# LEDRing.net
KiCad netlist of a schematic drawn in EAGLE
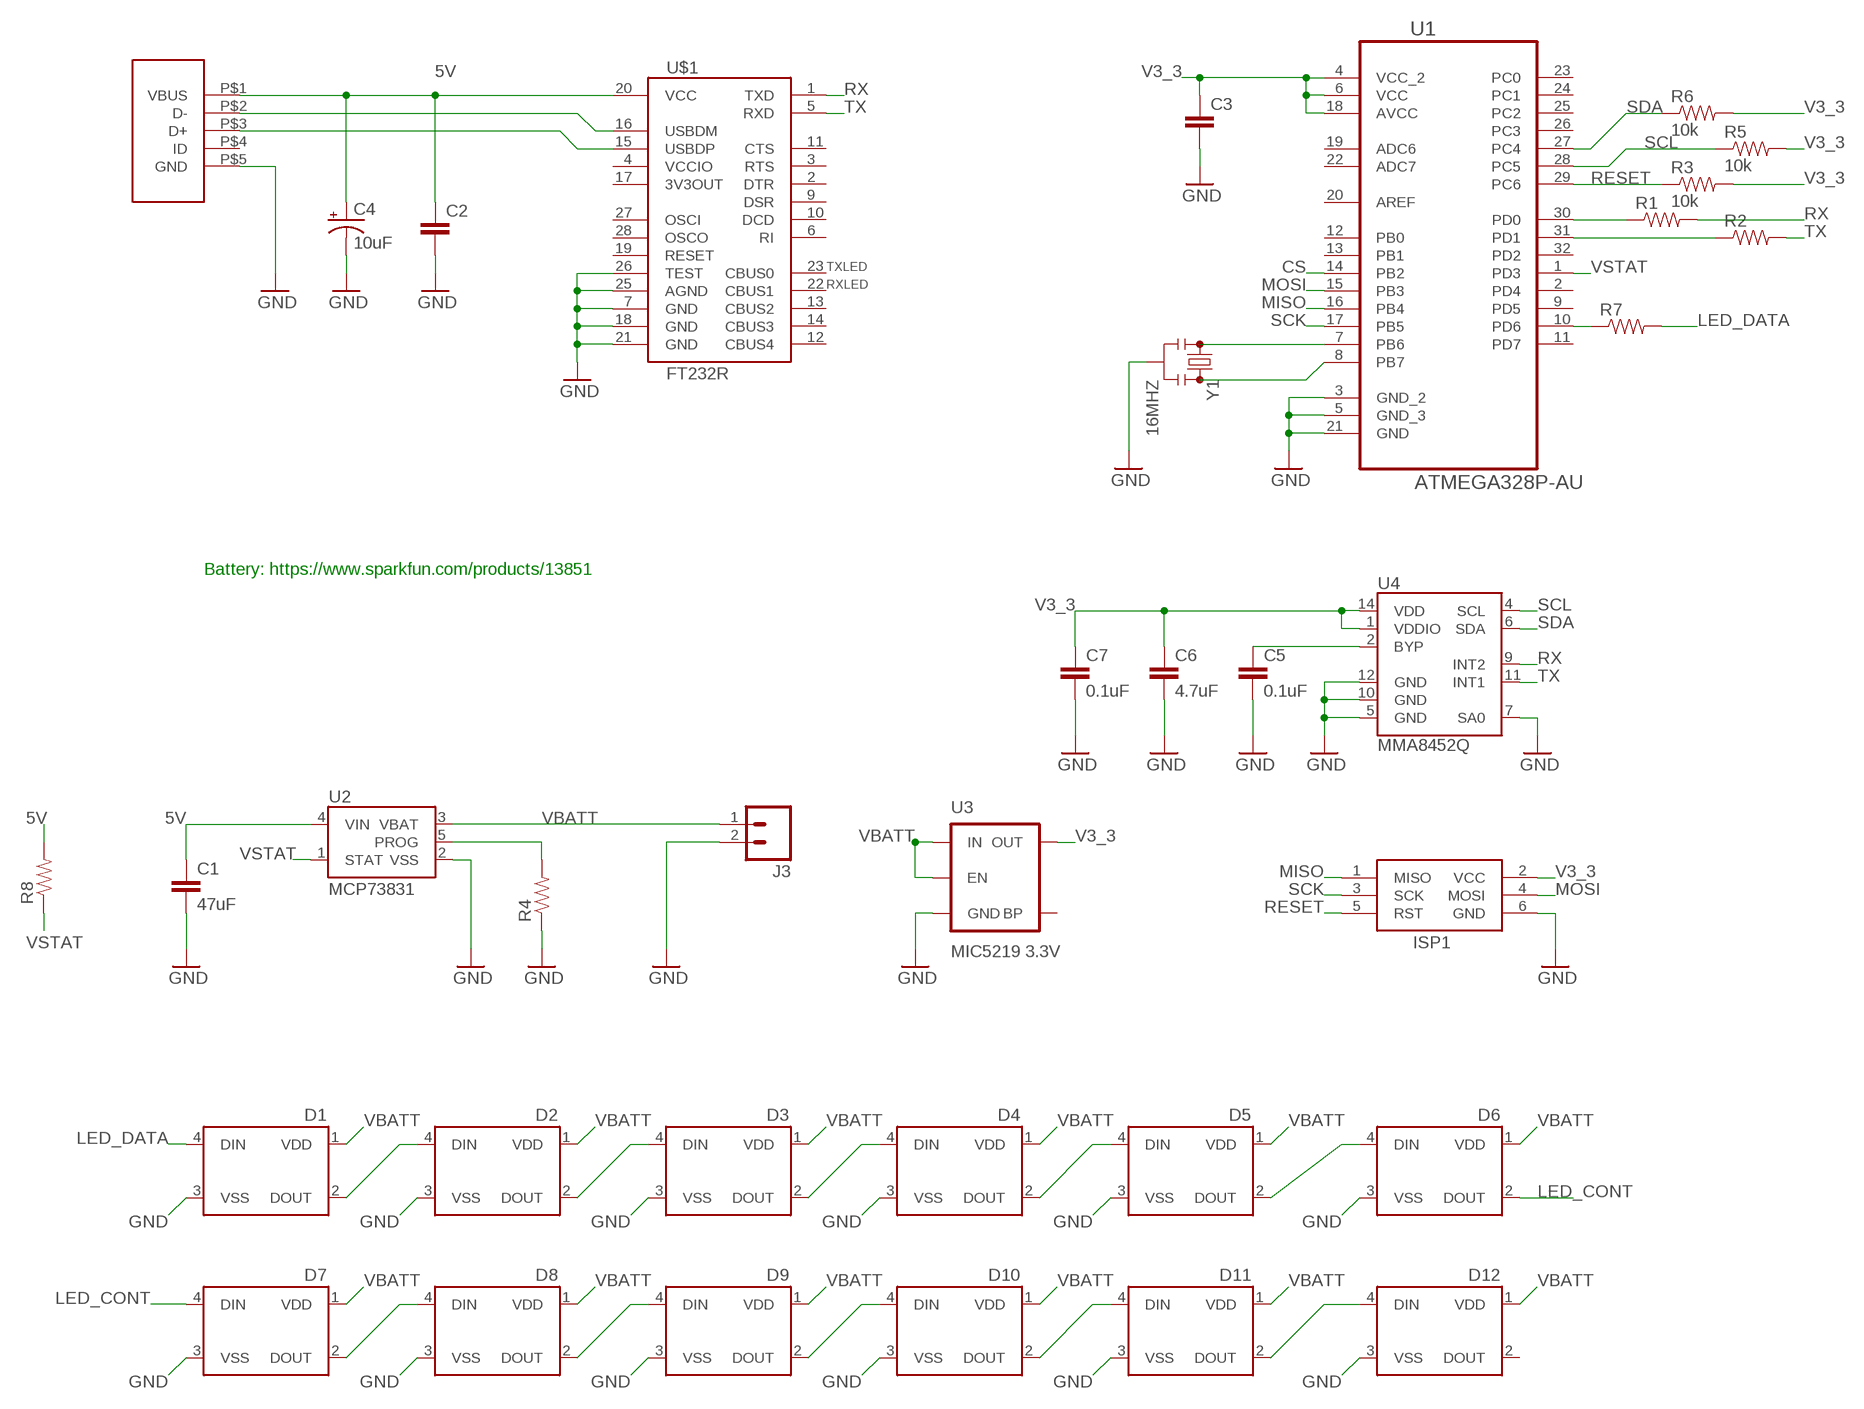
[diagram p0: schematic, sheet 1]

(export (version "E")
  (design (tool "Eeschema 10.0.6"))
  (components
    (comp (ref "C1")
      (value "47uF")
      (footprint "eagle-import:0603-CAP")
      (libsource (lib "eagle-import") (part "CAP0603-CAP"))
    )
    (comp (ref "C2")
      (value "CAP0603-CAP")
      (footprint "eagle-import:0603-CAP")
      (libsource (lib "eagle-import") (part "CAP0603-CAP"))
    )
    (comp (ref "C3")
      (value "CAP0603-CAP")
      (footprint "eagle-import:0603-CAP")
      (libsource (lib "eagle-import") (part "CAP0603-CAP"))
    )
    (comp (ref "C4")
      (value "10uF")
      (footprint "eagle-import:0603-POL")
      (libsource (lib "eagle-import") (part "10UF-6.3V-20%(0603)(TANT){dblquote}"))
    )
    (comp (ref "C5")
      (value "0.1uF")
      (footprint "eagle-import:0603-CAP")
      (libsource (lib "eagle-import") (part "CAP0603-CAP"))
    )
    (comp (ref "C6")
      (value "4.7uF")
      (footprint "eagle-import:0603-CAP")
      (libsource (lib "eagle-import") (part "CAP0603-CAP"))
    )
    (comp (ref "C7")
      (value "0.1uF")
      (footprint "eagle-import:0603-CAP")
      (libsource (lib "eagle-import") (part "CAP0603-CAP"))
    )
    (comp (ref "D1")
      (value "WS2812B")
      (footprint "eagle-import:WS2812B")
      (libsource (lib "eagle-import") (part "WS2812B"))
    )
    (comp (ref "D2")
      (value "WS2812B")
      (footprint "eagle-import:WS2812B")
      (libsource (lib "eagle-import") (part "WS2812B"))
    )
    (comp (ref "D3")
      (value "WS2812B")
      (footprint "eagle-import:WS2812B")
      (libsource (lib "eagle-import") (part "WS2812B"))
    )
    (comp (ref "D4")
      (value "WS2812B")
      (footprint "eagle-import:WS2812B")
      (libsource (lib "eagle-import") (part "WS2812B"))
    )
    (comp (ref "D5")
      (value "WS2812B")
      (footprint "eagle-import:WS2812B")
      (libsource (lib "eagle-import") (part "WS2812B"))
    )
    (comp (ref "D6")
      (value "WS2812B")
      (footprint "eagle-import:WS2812B")
      (libsource (lib "eagle-import") (part "WS2812B"))
    )
    (comp (ref "D7")
      (value "WS2812B")
      (footprint "eagle-import:WS2812B")
      (libsource (lib "eagle-import") (part "WS2812B"))
    )
    (comp (ref "D8")
      (value "WS2812B")
      (footprint "eagle-import:WS2812B")
      (libsource (lib "eagle-import") (part "WS2812B"))
    )
    (comp (ref "D9")
      (value "WS2812B")
      (footprint "eagle-import:WS2812B")
      (libsource (lib "eagle-import") (part "WS2812B"))
    )
    (comp (ref "D10")
      (value "WS2812B")
      (footprint "eagle-import:WS2812B")
      (libsource (lib "eagle-import") (part "WS2812B"))
    )
    (comp (ref "D11")
      (value "WS2812B")
      (footprint "eagle-import:WS2812B")
      (libsource (lib "eagle-import") (part "WS2812B"))
    )
    (comp (ref "D12")
      (value "WS2812B")
      (footprint "eagle-import:WS2812B")
      (libsource (lib "eagle-import") (part "WS2812B"))
    )
    (comp (ref "ISP1")
      (value "AVRISP-BOX")
      (footprint "eagle-import:AVRISP-BOX")
      (libsource (lib "eagle-import") (part "AVRISP-BOX"))
    )
    (comp (ref "J3")
      (value "M02PTH")
      (footprint "eagle-import:1X02")
      (libsource (lib "eagle-import") (part "M02PTH"))
    )
    (comp (ref "R1")
      (value "RESISTOR0603-RES")
      (footprint "eagle-import:0603-RES")
      (libsource (lib "eagle-import") (part "RESISTOR0603-RES"))
    )
    (comp (ref "R2")
      (value "RESISTOR0603-RES")
      (footprint "eagle-import:0603-RES")
      (libsource (lib "eagle-import") (part "RESISTOR0603-RES"))
    )
    (comp (ref "R3")
      (value "10k")
      (footprint "eagle-import:0603-RES")
      (libsource (lib "eagle-import") (part "RESISTOR0603-RES"))
    )
    (comp (ref "R4")
      (value "RESISTOR0603-RES")
      (footprint "eagle-import:0603-RES")
      (libsource (lib "eagle-import") (part "RESISTOR0603-RES"))
    )
    (comp (ref "R5")
      (value "10k")
      (footprint "eagle-import:0603-RES")
      (libsource (lib "eagle-import") (part "RESISTOR0603-RES"))
    )
    (comp (ref "R6")
      (value "10k")
      (footprint "eagle-import:0603-RES")
      (libsource (lib "eagle-import") (part "RESISTOR0603-RES"))
    )
    (comp (ref "R7")
      (value "RESISTOR0603-RES")
      (footprint "eagle-import:0603-RES")
      (libsource (lib "eagle-import") (part "RESISTOR0603-RES"))
    )
    (comp (ref "R8")
      (value "RESISTOR0603-RES")
      (footprint "eagle-import:0603-RES")
      (libsource (lib "eagle-import") (part "RESISTOR0603-RES"))
    )
    (comp (ref "U$1")
      (value "FT232R")
      (footprint "eagle-import:SSOP-28")
      (libsource (lib "eagle-import") (part "FT232R"))
    )
    (comp (ref "U$2")
      (value "TE_USB_A121025CT")
      (footprint "eagle-import:TE_USB_A121025CT")
      (libsource (lib "eagle-import") (part "TE_USB_A121025CT"))
    )
    (comp (ref "U1")
      (value "ATMEGA328P-AU")
      (footprint "eagle-import:QFP80P900X900X120-32N")
      (libsource (lib "eagle-import") (part "ATMEGA328P-AU"))
    )
    (comp (ref "U2")
      (value "MCP73831")
      (footprint "eagle-import:SOT23-5")
      (libsource (lib "eagle-import") (part "MCP73831"))
    )
    (comp (ref "U3")
      (value "MIC5219 3.3V")
      (footprint "eagle-import:SOT23-5")
      (libsource (lib "eagle-import") (part "V_REG_MIC52193.3V"))
    )
    (comp (ref "U4")
      (value "MMA8452Q")
      (footprint "eagle-import:QFN-16_0.5MM")
      (libsource (lib "eagle-import") (part "MMA8452Q"))
    )
    (comp (ref "Y1")
      (value "16MHZ")
      (footprint "eagle-import:RESONATOR-SMD")
      (libsource (lib "eagle-import") (part "RESONATOR16MHZ"))
    )
  )
  (nets
    (net (code "1") (name "/5V") (class "Default")
      (node (ref "C1") (pin "1") (pinfunction "1_1") (pintype "passive"))
      (node (ref "C2") (pin "1") (pinfunction "1_1") (pintype "passive"))
      (node (ref "C4") (pin "A") (pinfunction "+_A") (pintype "passive"))
      (node (ref "R8") (pin "2") (pinfunction "2_2") (pintype "passive"))
      (node (ref "U$1") (pin "20") (pinfunction "VCC_20") (pintype "power_in"))
      (node (ref "U$2") (pin "P$1") (pinfunction "VBUS_P$1") (pintype "bidirectional"))
      (node (ref "U2") (pin "4") (pinfunction "VIN_4") (pintype "power_in"))
    )
    (net (code "2") (name "/CS") (class "Default")
      (node (ref "U1") (pin "14") (pinfunction "PB2_14") (pintype "bidirectional"))
    )
    (net (code "3") (name "/LED_CONT") (class "Default")
      (node (ref "D6") (pin "2") (pinfunction "DOUT_2") (pintype "output"))
      (node (ref "D7") (pin "4") (pinfunction "DIN_4") (pintype "input"))
    )
    (net (code "4") (name "/LED_DATA") (class "Default")
      (node (ref "D1") (pin "4") (pinfunction "DIN_4") (pintype "input"))
      (node (ref "R7") (pin "2") (pinfunction "2_2") (pintype "passive"))
    )
    (net (code "5") (name "/MISO") (class "Default")
      (node (ref "ISP1") (pin "1") (pinfunction "MISO_1") (pintype "input"))
      (node (ref "U1") (pin "16") (pinfunction "PB4_16") (pintype "bidirectional"))
    )
    (net (code "6") (name "/MOSI") (class "Default")
      (node (ref "ISP1") (pin "4") (pinfunction "MOSI_4") (pintype "output"))
      (node (ref "U1") (pin "15") (pinfunction "PB3_15") (pintype "bidirectional"))
    )
    (net (code "7") (name "/RESET") (class "Default")
      (node (ref "ISP1") (pin "5") (pinfunction "RST_5") (pintype "output"))
      (node (ref "R3") (pin "1") (pinfunction "1_1") (pintype "passive"))
      (node (ref "U1") (pin "29") (pinfunction "PC6_29") (pintype "bidirectional"))
    )
    (net (code "8") (name "/RX") (class "Default")
      (node (ref "R1") (pin "2") (pinfunction "2_2") (pintype "passive"))
      (node (ref "U$1") (pin "1") (pinfunction "TXD_1") (pintype "output"))
      (node (ref "U4") (pin "9") (pinfunction "INT2_9") (pintype "bidirectional"))
    )
    (net (code "9") (name "/SCK") (class "Default")
      (node (ref "ISP1") (pin "3") (pinfunction "SCK_3") (pintype "output"))
      (node (ref "U1") (pin "17") (pinfunction "PB5_17") (pintype "bidirectional"))
    )
    (net (code "10") (name "/SCL") (class "Default")
      (node (ref "R5") (pin "1") (pinfunction "1_1") (pintype "passive"))
      (node (ref "U1") (pin "28") (pinfunction "PC5_28") (pintype "bidirectional"))
      (node (ref "U4") (pin "4") (pinfunction "SCL_4") (pintype "bidirectional"))
    )
    (net (code "11") (name "/SDA") (class "Default")
      (node (ref "R6") (pin "1") (pinfunction "1_1") (pintype "passive"))
      (node (ref "U1") (pin "27") (pinfunction "PC4_27") (pintype "bidirectional"))
      (node (ref "U4") (pin "6") (pinfunction "SDA_6") (pintype "bidirectional"))
    )
    (net (code "12") (name "/TX") (class "Default")
      (node (ref "R2") (pin "2") (pinfunction "2_2") (pintype "passive"))
      (node (ref "U$1") (pin "5") (pinfunction "RXD_5") (pintype "input"))
      (node (ref "U4") (pin "11") (pinfunction "INT1_11") (pintype "bidirectional"))
    )
    (net (code "13") (name "/V3_3") (class "Default")
      (node (ref "C3") (pin "1") (pinfunction "1_1") (pintype "passive"))
      (node (ref "C6") (pin "1") (pinfunction "1_1") (pintype "passive"))
      (node (ref "C7") (pin "1") (pinfunction "1_1") (pintype "passive"))
      (node (ref "ISP1") (pin "2") (pinfunction "VCC_2") (pintype "power_in"))
      (node (ref "R3") (pin "2") (pinfunction "2_2") (pintype "passive"))
      (node (ref "R5") (pin "2") (pinfunction "2_2") (pintype "passive"))
      (node (ref "R6") (pin "2") (pinfunction "2_2") (pintype "passive"))
      (node (ref "U1") (pin "18") (pinfunction "AVCC_18") (pintype "power_in"))
      (node (ref "U1") (pin "4") (pinfunction "VCC_2_4") (pintype "power_in"))
      (node (ref "U1") (pin "6") (pinfunction "VCC_6") (pintype "power_in"))
      (node (ref "U3") (pin "5") (pinfunction "OUT_5") (pintype "passive"))
      (node (ref "U4") (pin "1") (pinfunction "VDDIO_1") (pintype "bidirectional"))
      (node (ref "U4") (pin "14") (pinfunction "VDD_14") (pintype "bidirectional"))
    )
    (net (code "14") (name "/VBATT") (class "Default")
      (node (ref "D1") (pin "1") (pinfunction "VDD_1") (pintype "power_in"))
      (node (ref "D10") (pin "1") (pinfunction "VDD_1") (pintype "power_in"))
      (node (ref "D11") (pin "1") (pinfunction "VDD_1") (pintype "power_in"))
      (node (ref "D12") (pin "1") (pinfunction "VDD_1") (pintype "power_in"))
      (node (ref "D2") (pin "1") (pinfunction "VDD_1") (pintype "power_in"))
      (node (ref "D3") (pin "1") (pinfunction "VDD_1") (pintype "power_in"))
      (node (ref "D4") (pin "1") (pinfunction "VDD_1") (pintype "power_in"))
      (node (ref "D5") (pin "1") (pinfunction "VDD_1") (pintype "power_in"))
      (node (ref "D6") (pin "1") (pinfunction "VDD_1") (pintype "power_in"))
      (node (ref "D7") (pin "1") (pinfunction "VDD_1") (pintype "power_in"))
      (node (ref "D8") (pin "1") (pinfunction "VDD_1") (pintype "power_in"))
      (node (ref "D9") (pin "1") (pinfunction "VDD_1") (pintype "power_in"))
      (node (ref "J3") (pin "1") (pinfunction "1_1") (pintype "passive"))
      (node (ref "U2") (pin "3") (pinfunction "VBAT_3") (pintype "power_in"))
      (node (ref "U3") (pin "1") (pinfunction "IN_1") (pintype "input"))
      (node (ref "U3") (pin "3") (pinfunction "EN_3") (pintype "input"))
    )
    (net (code "15") (name "/VCCIO") (class "Default")
      (node (ref "U$1") (pin "4") (pinfunction "VCCIO_4") (pintype "power_in"))
    )
    (net (code "16") (name "/VSTAT") (class "Default")
      (node (ref "R8") (pin "1") (pinfunction "1_1") (pintype "passive"))
      (node (ref "U1") (pin "1") (pinfunction "PD3_1") (pintype "bidirectional"))
      (node (ref "U2") (pin "1") (pinfunction "STAT_1") (pintype "output"))
    )
    (net (code "17") (name "GND") (class "Default")
      (node (ref "C1") (pin "2") (pinfunction "2_2") (pintype "passive"))
      (node (ref "C2") (pin "2") (pinfunction "2_2") (pintype "passive"))
      (node (ref "C3") (pin "2") (pinfunction "2_2") (pintype "passive"))
      (node (ref "C4") (pin "K") (pinfunction "-_K") (pintype "passive"))
      (node (ref "C5") (pin "2") (pinfunction "2_2") (pintype "passive"))
      (node (ref "C6") (pin "2") (pinfunction "2_2") (pintype "passive"))
      (node (ref "C7") (pin "2") (pinfunction "2_2") (pintype "passive"))
      (node (ref "D1") (pin "3") (pinfunction "VSS_3") (pintype "power_in"))
      (node (ref "D10") (pin "3") (pinfunction "VSS_3") (pintype "power_in"))
      (node (ref "D11") (pin "3") (pinfunction "VSS_3") (pintype "power_in"))
      (node (ref "D12") (pin "3") (pinfunction "VSS_3") (pintype "power_in"))
      (node (ref "D2") (pin "3") (pinfunction "VSS_3") (pintype "power_in"))
      (node (ref "D3") (pin "3") (pinfunction "VSS_3") (pintype "power_in"))
      (node (ref "D4") (pin "3") (pinfunction "VSS_3") (pintype "power_in"))
      (node (ref "D5") (pin "3") (pinfunction "VSS_3") (pintype "power_in"))
      (node (ref "D6") (pin "3") (pinfunction "VSS_3") (pintype "power_in"))
      (node (ref "D7") (pin "3") (pinfunction "VSS_3") (pintype "power_in"))
      (node (ref "D8") (pin "3") (pinfunction "VSS_3") (pintype "power_in"))
      (node (ref "D9") (pin "3") (pinfunction "VSS_3") (pintype "power_in"))
      (node (ref "ISP1") (pin "6") (pinfunction "GND_6") (pintype "power_in"))
      (node (ref "J3") (pin "2") (pinfunction "2_2") (pintype "passive"))
      (node (ref "R4") (pin "1") (pinfunction "1_1") (pintype "passive"))
      (node (ref "U$1") (pin "18") (pinfunction "GND_18") (pintype "power_in"))
      (node (ref "U$1") (pin "21") (pinfunction "GND_21") (pintype "power_in"))
      (node (ref "U$1") (pin "25") (pinfunction "AGND_25") (pintype "power_in"))
      (node (ref "U$1") (pin "26") (pinfunction "TEST_26") (pintype "input"))
      (node (ref "U$1") (pin "7") (pinfunction "GND_7") (pintype "power_in"))
      (node (ref "U$2") (pin "P$5") (pinfunction "GND_P$5") (pintype "bidirectional"))
      (node (ref "U1") (pin "21") (pinfunction "GND_21") (pintype "passive"))
      (node (ref "U1") (pin "3") (pinfunction "GND_2_3") (pintype "passive"))
      (node (ref "U1") (pin "5") (pinfunction "GND_3_5") (pintype "passive"))
      (node (ref "U2") (pin "2") (pinfunction "VSS_2") (pintype "power_in"))
      (node (ref "U3") (pin "2") (pinfunction "GND_2") (pintype "input"))
      (node (ref "U4") (pin "10") (pinfunction "GND_10") (pintype "bidirectional"))
      (node (ref "U4") (pin "12") (pinfunction "GND_12") (pintype "bidirectional"))
      (node (ref "U4") (pin "5") (pinfunction "GND_5") (pintype "bidirectional"))
      (node (ref "U4") (pin "7") (pinfunction "SA0_7") (pintype "bidirectional"))
      (node (ref "Y1") (pin "2") (pinfunction "2_2") (pintype "passive"))
    )
    (net (code "18") (name "Net-(D1-DOUT)") (class "Default")
      (node (ref "D1") (pin "2") (pinfunction "DOUT_2") (pintype "output"))
      (node (ref "D2") (pin "4") (pinfunction "DIN_4") (pintype "input"))
    )
    (net (code "19") (name "Net-(D2-DOUT)") (class "Default")
      (node (ref "D2") (pin "2") (pinfunction "DOUT_2") (pintype "output"))
      (node (ref "D3") (pin "4") (pinfunction "DIN_4") (pintype "input"))
    )
    (net (code "20") (name "Net-(D3-DOUT)") (class "Default")
      (node (ref "D3") (pin "2") (pinfunction "DOUT_2") (pintype "output"))
      (node (ref "D4") (pin "4") (pinfunction "DIN_4") (pintype "input"))
    )
    (net (code "21") (name "Net-(D4-DOUT)") (class "Default")
      (node (ref "D4") (pin "2") (pinfunction "DOUT_2") (pintype "output"))
      (node (ref "D5") (pin "4") (pinfunction "DIN_4") (pintype "input"))
    )
    (net (code "22") (name "Net-(D5-DOUT)") (class "Default")
      (node (ref "D5") (pin "2") (pinfunction "DOUT_2") (pintype "output"))
      (node (ref "D6") (pin "4") (pinfunction "DIN_4") (pintype "input"))
    )
    (net (code "23") (name "Net-(D7-DOUT)") (class "Default")
      (node (ref "D7") (pin "2") (pinfunction "DOUT_2") (pintype "output"))
      (node (ref "D8") (pin "4") (pinfunction "DIN_4") (pintype "input"))
    )
    (net (code "24") (name "Net-(D8-DOUT)") (class "Default")
      (node (ref "D8") (pin "2") (pinfunction "DOUT_2") (pintype "output"))
      (node (ref "D9") (pin "4") (pinfunction "DIN_4") (pintype "input"))
    )
    (net (code "25") (name "Net-(D10-DIN)") (class "Default")
      (node (ref "D10") (pin "4") (pinfunction "DIN_4") (pintype "input"))
      (node (ref "D9") (pin "2") (pinfunction "DOUT_2") (pintype "output"))
    )
    (net (code "26") (name "Net-(D10-DOUT)") (class "Default")
      (node (ref "D10") (pin "2") (pinfunction "DOUT_2") (pintype "output"))
      (node (ref "D11") (pin "4") (pinfunction "DIN_4") (pintype "input"))
    )
    (net (code "27") (name "Net-(D11-DOUT)") (class "Default")
      (node (ref "D11") (pin "2") (pinfunction "DOUT_2") (pintype "output"))
      (node (ref "D12") (pin "4") (pinfunction "DIN_4") (pintype "input"))
    )
    (net (code "28") (name "Net-(U$1-USBDM)") (class "Default")
      (node (ref "U$1") (pin "16") (pinfunction "USBDM_16") (pintype "bidirectional"))
      (node (ref "U$2") (pin "P$2") (pinfunction "D-_P$2") (pintype "bidirectional"))
    )
    (net (code "29") (name "Net-(U$1-USBDP)") (class "Default")
      (node (ref "U$1") (pin "15") (pinfunction "USBDP_15") (pintype "bidirectional"))
      (node (ref "U$2") (pin "P$3") (pinfunction "D+_P$3") (pintype "bidirectional"))
    )
    (net (code "30") (name "Net-(U1-PB6)") (class "Default")
      (node (ref "U1") (pin "7") (pinfunction "PB6_7") (pintype "bidirectional"))
      (node (ref "Y1") (pin "1") (pinfunction "1_1") (pintype "passive"))
    )
    (net (code "31") (name "Net-(U1-PB7)") (class "Default")
      (node (ref "U1") (pin "8") (pinfunction "PB7_8") (pintype "bidirectional"))
      (node (ref "Y1") (pin "3") (pinfunction "3_3") (pintype "passive"))
    )
    (net (code "32") (name "Net-(U1-PD0)") (class "Default")
      (node (ref "R1") (pin "1") (pinfunction "1_1") (pintype "passive"))
      (node (ref "U1") (pin "30") (pinfunction "PD0_30") (pintype "bidirectional"))
    )
    (net (code "33") (name "Net-(U1-PD1)") (class "Default")
      (node (ref "R2") (pin "1") (pinfunction "1_1") (pintype "passive"))
      (node (ref "U1") (pin "31") (pinfunction "PD1_31") (pintype "bidirectional"))
    )
    (net (code "34") (name "Net-(U1-PD6)") (class "Default")
      (node (ref "R7") (pin "1") (pinfunction "1_1") (pintype "passive"))
      (node (ref "U1") (pin "10") (pinfunction "PD6_10") (pintype "bidirectional"))
    )
    (net (code "35") (name "Net-(U2-PROG)") (class "Default")
      (node (ref "R4") (pin "2") (pinfunction "2_2") (pintype "passive"))
      (node (ref "U2") (pin "5") (pinfunction "PROG_5") (pintype "input"))
    )
    (net (code "36") (name "Net-(U4-BYP)") (class "Default")
      (node (ref "C5") (pin "1") (pinfunction "1_1") (pintype "passive"))
      (node (ref "U4") (pin "2") (pinfunction "BYP_2") (pintype "bidirectional"))
    )
    (net (code "37") (name "unconnected-(D12-DOUT-Pad2)") (class "Default")
      (node (ref "D12") (pin "2") (pinfunction "DOUT_2") (pintype "output"))
    )
    (net (code "38") (name "unconnected-(U$1-3V3OUT-Pad17)") (class "Default")
      (node (ref "U$1") (pin "17") (pinfunction "3V3OUT_17") (pintype "output"))
    )
    (net (code "39") (name "unconnected-(U$1-CBUS0-Pad23)") (class "Default")
      (node (ref "U$1") (pin "23") (pinfunction "CBUS0_23") (pintype "input"))
    )
    (net (code "40") (name "unconnected-(U$1-CBUS1-Pad22)") (class "Default")
      (node (ref "U$1") (pin "22") (pinfunction "CBUS1_22") (pintype "input"))
    )
    (net (code "41") (name "unconnected-(U$1-CBUS2-Pad13)") (class "Default")
      (node (ref "U$1") (pin "13") (pinfunction "CBUS2_13") (pintype "input"))
    )
    (net (code "42") (name "unconnected-(U$1-CBUS3-Pad14)") (class "Default")
      (node (ref "U$1") (pin "14") (pinfunction "CBUS3_14") (pintype "input"))
    )
    (net (code "43") (name "unconnected-(U$1-CBUS4-Pad12)") (class "Default")
      (node (ref "U$1") (pin "12") (pinfunction "CBUS4_12") (pintype "input"))
    )
    (net (code "44") (name "unconnected-(U$1-CTS-Pad11)") (class "Default")
      (node (ref "U$1") (pin "11") (pinfunction "CTS_11") (pintype "input"))
    )
    (net (code "45") (name "unconnected-(U$1-DCD-Pad10)") (class "Default")
      (node (ref "U$1") (pin "10") (pinfunction "DCD_10") (pintype "input"))
    )
    (net (code "46") (name "unconnected-(U$1-DSR-Pad9)") (class "Default")
      (node (ref "U$1") (pin "9") (pinfunction "DSR_9") (pintype "input"))
    )
    (net (code "47") (name "unconnected-(U$1-DTR-Pad2)") (class "Default")
      (node (ref "U$1") (pin "2") (pinfunction "DTR_2") (pintype "output"))
    )
    (net (code "48") (name "unconnected-(U$1-OSCI-Pad27)") (class "Default")
      (node (ref "U$1") (pin "27") (pinfunction "OSCI_27") (pintype "input"))
    )
    (net (code "49") (name "unconnected-(U$1-OSCO-Pad28)") (class "Default")
      (node (ref "U$1") (pin "28") (pinfunction "OSCO_28") (pintype "output"))
    )
    (net (code "50") (name "unconnected-(U$1-RESET-Pad19)") (class "Default")
      (node (ref "U$1") (pin "19") (pinfunction "RESET_19") (pintype "input"))
    )
    (net (code "51") (name "unconnected-(U$1-RI-Pad6)") (class "Default")
      (node (ref "U$1") (pin "6") (pinfunction "RI_6") (pintype "input"))
    )
    (net (code "52") (name "unconnected-(U$1-RTS-Pad3)") (class "Default")
      (node (ref "U$1") (pin "3") (pinfunction "RTS_3") (pintype "output"))
    )
    (net (code "53") (name "unconnected-(U$2-ID-PadP$4)") (class "Default")
      (node (ref "U$2") (pin "P$4") (pinfunction "ID_P$4") (pintype "bidirectional"))
    )
    (net (code "54") (name "unconnected-(U1-ADC6-Pad19)") (class "Default")
      (node (ref "U1") (pin "19") (pinfunction "ADC6_19") (pintype "input"))
    )
    (net (code "55") (name "unconnected-(U1-ADC7-Pad22)") (class "Default")
      (node (ref "U1") (pin "22") (pinfunction "ADC7_22") (pintype "input"))
    )
    (net (code "56") (name "unconnected-(U1-AREF-Pad20)") (class "Default")
      (node (ref "U1") (pin "20") (pinfunction "AREF_20") (pintype "input"))
    )
    (net (code "57") (name "unconnected-(U1-PB0-Pad12)") (class "Default")
      (node (ref "U1") (pin "12") (pinfunction "PB0_12") (pintype "bidirectional"))
    )
    (net (code "58") (name "unconnected-(U1-PB1-Pad13)") (class "Default")
      (node (ref "U1") (pin "13") (pinfunction "PB1_13") (pintype "bidirectional"))
    )
    (net (code "59") (name "unconnected-(U1-PC0-Pad23)") (class "Default")
      (node (ref "U1") (pin "23") (pinfunction "PC0_23") (pintype "bidirectional"))
    )
    (net (code "60") (name "unconnected-(U1-PC1-Pad24)") (class "Default")
      (node (ref "U1") (pin "24") (pinfunction "PC1_24") (pintype "bidirectional"))
    )
    (net (code "61") (name "unconnected-(U1-PC2-Pad25)") (class "Default")
      (node (ref "U1") (pin "25") (pinfunction "PC2_25") (pintype "bidirectional"))
    )
    (net (code "62") (name "unconnected-(U1-PC3-Pad26)") (class "Default")
      (node (ref "U1") (pin "26") (pinfunction "PC3_26") (pintype "bidirectional"))
    )
    (net (code "63") (name "unconnected-(U1-PD2-Pad32)") (class "Default")
      (node (ref "U1") (pin "32") (pinfunction "PD2_32") (pintype "bidirectional"))
    )
    (net (code "64") (name "unconnected-(U1-PD4-Pad2)") (class "Default")
      (node (ref "U1") (pin "2") (pinfunction "PD4_2") (pintype "bidirectional"))
    )
    (net (code "65") (name "unconnected-(U1-PD5-Pad9)") (class "Default")
      (node (ref "U1") (pin "9") (pinfunction "PD5_9") (pintype "bidirectional"))
    )
    (net (code "66") (name "unconnected-(U1-PD7-Pad11)") (class "Default")
      (node (ref "U1") (pin "11") (pinfunction "PD7_11") (pintype "bidirectional"))
    )
    (net (code "67") (name "unconnected-(U3-BP-Pad4)") (class "Default")
      (node (ref "U3") (pin "4") (pinfunction "BP_4") (pintype "input"))
    )
  )
)
